# LCD.net
KiCad netlist of a schematic drawn in Altium Designer
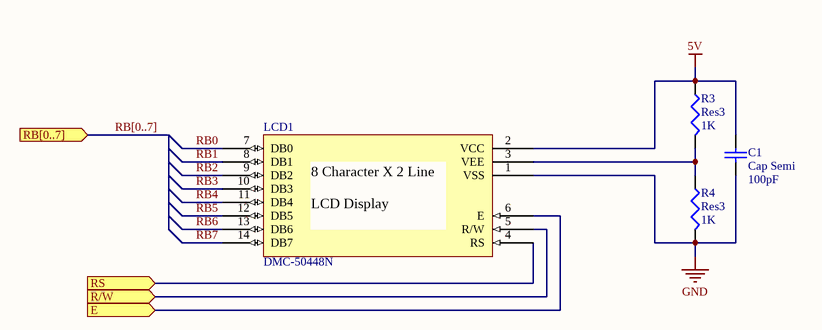
[diagram p0: LCD.SchDoc]

(export (version "E")
  (design (tool "Eeschema 10.0.6"))
  (components
    (comp (ref "C1")
      (value "Cap Semi")
      (footprint "0603_C")
      (description "Capacitor (Semiconductor SIM Model)")
      (fields (field (name "ALTIUM_VALUE") "100pF") (field (name "PUBLISHER") "Altium Limited"))
      (libsource (lib "Miscellaneous Devices") (part "Cap Semi"))
    )
    (comp (ref "LCD1")
      (value "DMC-50448N")
      (footprint "HDR1X14")
      (description "8 Character X 2 Line\r\nLCD Display")
      (libsource (lib "ad_test2_IntLib") (part "DMC-50448N"))
    )
    (comp (ref "R3")
      (value "Res3")
      (footprint "0603_R")
      (description "Resistor")
      (fields (field (name "ALTIUM_VALUE") "1K") (field (name "PUBLISHER") "Altium Limited"))
      (libsource (lib "Miscellaneous Devices") (part "Res3"))
    )
    (comp (ref "R4")
      (value "Res3")
      (footprint "0603_R")
      (description "Resistor")
      (fields (field (name "ALTIUM_VALUE") "1K") (field (name "PUBLISHER") "Altium Limited"))
      (libsource (lib "Miscellaneous Devices") (part "Res3"))
    )
  )
  (nets
    (net (code "1") (name "/E") (class "Default")
      (node (ref "LCD1") (pin "6") (pinfunction "E_6") (pintype "input"))
    )
    (net (code "2") (name "/RB0") (class "Default")
      (node (ref "LCD1") (pin "7") (pinfunction "DB0_7") (pintype "bidirectional"))
    )
    (net (code "3") (name "/RB1") (class "Default")
      (node (ref "LCD1") (pin "8") (pinfunction "DB1_8") (pintype "bidirectional"))
    )
    (net (code "4") (name "/RB2") (class "Default")
      (node (ref "LCD1") (pin "9") (pinfunction "DB2_9") (pintype "bidirectional"))
    )
    (net (code "5") (name "/RB3") (class "Default")
      (node (ref "LCD1") (pin "10") (pinfunction "DB3_10") (pintype "bidirectional"))
    )
    (net (code "6") (name "/RB4") (class "Default")
      (node (ref "LCD1") (pin "11") (pinfunction "DB4_11") (pintype "bidirectional"))
    )
    (net (code "7") (name "/RB5") (class "Default")
      (node (ref "LCD1") (pin "12") (pinfunction "DB5_12") (pintype "bidirectional"))
    )
    (net (code "8") (name "/RB6") (class "Default")
      (node (ref "LCD1") (pin "13") (pinfunction "DB6_13") (pintype "bidirectional"))
    )
    (net (code "9") (name "/RB7") (class "Default")
      (node (ref "LCD1") (pin "14") (pinfunction "DB7_14") (pintype "bidirectional"))
    )
    (net (code "11") (name "/RS") (class "Default")
      (node (ref "LCD1") (pin "4") (pinfunction "RS_4") (pintype "input"))
    )
    (net (code "12") (name "/R{slash}W") (class "Default")
      (node (ref "LCD1") (pin "5") (pinfunction "R/W_5") (pintype "input"))
    )
    (net (code "13") (name "5V") (class "Default")
      (node (ref "C1") (pin "2") (pinfunction "2_2") (pintype "passive"))
      (node (ref "LCD1") (pin "2") (pinfunction "VCC_2") (pintype "power_in"))
      (node (ref "R3") (pin "1") (pinfunction "1_1") (pintype "passive"))
    )
    (net (code "14") (name "GND") (class "Default")
      (node (ref "C1") (pin "1") (pinfunction "1_1") (pintype "passive"))
      (node (ref "LCD1") (pin "1") (pinfunction "VSS_1") (pintype "power_in"))
      (node (ref "R4") (pin "2") (pinfunction "2_2") (pintype "passive"))
    )
    (net (code "15") (name "Net-(LCD1-VEE)") (class "Default")
      (node (ref "LCD1") (pin "3") (pinfunction "VEE_3") (pintype "power_in"))
      (node (ref "R3") (pin "2") (pinfunction "2_2") (pintype "passive"))
      (node (ref "R4") (pin "1") (pinfunction "1_1") (pintype "passive"))
    )
  )
)
